# l293_board.net
KiCad netlist of a schematic drawn in EAGLE
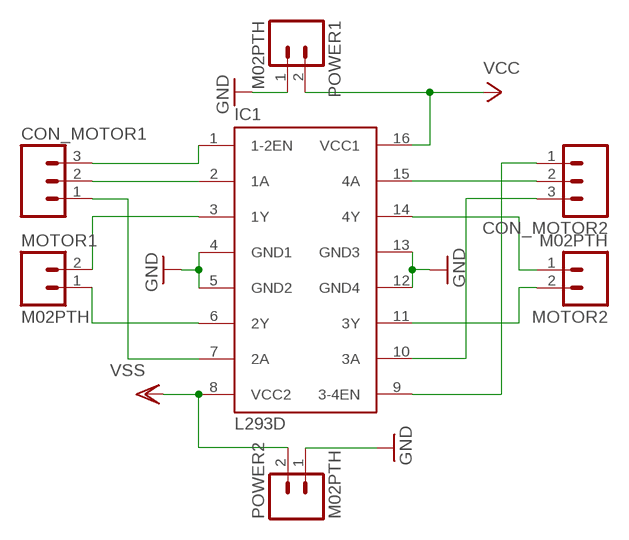
[diagram p0: schematic, sheet 1]

(export (version "E")
  (design (tool "Eeschema 10.0.6"))
  (components
    (comp (ref "CON_MOTOR1")
      (value "M03PTH")
      (footprint "eagle-import:1X03")
      (libsource (lib "eagle-import") (part "M03PTH"))
    )
    (comp (ref "CON_MOTOR2")
      (value "M03PTH")
      (footprint "eagle-import:1X03")
      (libsource (lib "eagle-import") (part "M03PTH"))
    )
    (comp (ref "IC1")
      (value "L293D")
      (footprint "eagle-import:DIL16")
      (libsource (lib "eagle-import") (part "L293D"))
    )
    (comp (ref "MOTOR1")
      (value "M02PTH")
      (footprint "eagle-import:1X02")
      (libsource (lib "eagle-import") (part "M02PTH"))
    )
    (comp (ref "MOTOR2")
      (value "M02PTH")
      (footprint "eagle-import:1X02")
      (libsource (lib "eagle-import") (part "M02PTH"))
    )
    (comp (ref "POWER1")
      (value "M02PTH")
      (footprint "eagle-import:1X02")
      (libsource (lib "eagle-import") (part "M02PTH"))
    )
    (comp (ref "POWER2")
      (value "M02PTH")
      (footprint "eagle-import:1X02")
      (libsource (lib "eagle-import") (part "M02PTH"))
    )
  )
  (nets
    (net (code "1") (name "GND") (class "Default")
      (node (ref "IC1") (pin "12") (pinfunction "GND4_12") (pintype "power_in"))
      (node (ref "IC1") (pin "13") (pinfunction "GND3_13") (pintype "power_in"))
      (node (ref "IC1") (pin "4") (pinfunction "GND1_4") (pintype "power_in"))
      (node (ref "IC1") (pin "5") (pinfunction "GND2_5") (pintype "power_in"))
      (node (ref "POWER1") (pin "1") (pinfunction "1_1") (pintype "passive"))
      (node (ref "POWER2") (pin "1") (pinfunction "1_1") (pintype "passive"))
    )
    (net (code "2") (name "Net-(IC1-1-2EN)") (class "Default")
      (node (ref "CON_MOTOR1") (pin "3") (pinfunction "3_3") (pintype "passive"))
      (node (ref "IC1") (pin "1") (pinfunction "1-2EN_1") (pintype "input"))
    )
    (net (code "3") (name "Net-(IC1-1A)") (class "Default")
      (node (ref "CON_MOTOR1") (pin "2") (pinfunction "2_2") (pintype "passive"))
      (node (ref "IC1") (pin "2") (pinfunction "1A_2") (pintype "input"))
    )
    (net (code "4") (name "Net-(IC1-1Y)") (class "Default")
      (node (ref "IC1") (pin "3") (pinfunction "1Y_3") (pintype "output"))
      (node (ref "MOTOR1") (pin "2") (pinfunction "2_2") (pintype "passive"))
    )
    (net (code "5") (name "Net-(IC1-2A)") (class "Default")
      (node (ref "CON_MOTOR1") (pin "1") (pinfunction "1_1") (pintype "passive"))
      (node (ref "IC1") (pin "7") (pinfunction "2A_7") (pintype "input"))
    )
    (net (code "6") (name "Net-(IC1-2Y)") (class "Default")
      (node (ref "IC1") (pin "6") (pinfunction "2Y_6") (pintype "output"))
      (node (ref "MOTOR1") (pin "1") (pinfunction "1_1") (pintype "passive"))
    )
    (net (code "7") (name "Net-(IC1-3-4EN)") (class "Default")
      (node (ref "CON_MOTOR2") (pin "1") (pinfunction "1_1") (pintype "passive"))
      (node (ref "IC1") (pin "9") (pinfunction "3-4EN_9") (pintype "input"))
    )
    (net (code "8") (name "Net-(IC1-3A)") (class "Default")
      (node (ref "CON_MOTOR2") (pin "3") (pinfunction "3_3") (pintype "passive"))
      (node (ref "IC1") (pin "10") (pinfunction "3A_10") (pintype "input"))
    )
    (net (code "9") (name "Net-(IC1-3Y)") (class "Default")
      (node (ref "IC1") (pin "11") (pinfunction "3Y_11") (pintype "output"))
      (node (ref "MOTOR2") (pin "2") (pinfunction "2_2") (pintype "passive"))
    )
    (net (code "10") (name "Net-(IC1-4A)") (class "Default")
      (node (ref "CON_MOTOR2") (pin "2") (pinfunction "2_2") (pintype "passive"))
      (node (ref "IC1") (pin "15") (pinfunction "4A_15") (pintype "input"))
    )
    (net (code "11") (name "Net-(IC1-4Y)") (class "Default")
      (node (ref "IC1") (pin "14") (pinfunction "4Y_14") (pintype "output"))
      (node (ref "MOTOR2") (pin "1") (pinfunction "1_1") (pintype "passive"))
    )
    (net (code "12") (name "VCC") (class "Default")
      (node (ref "IC1") (pin "16") (pinfunction "VCC1_16") (pintype "power_in"))
      (node (ref "POWER1") (pin "2") (pinfunction "2_2") (pintype "passive"))
    )
    (net (code "13") (name "VSS") (class "Default")
      (node (ref "IC1") (pin "8") (pinfunction "VCC2_8") (pintype "power_in"))
      (node (ref "POWER2") (pin "2") (pinfunction "2_2") (pintype "passive"))
    )
  )
)
